# CH32F203RCT6-R1.net
KiCad netlist of a schematic drawn in Altium Designer
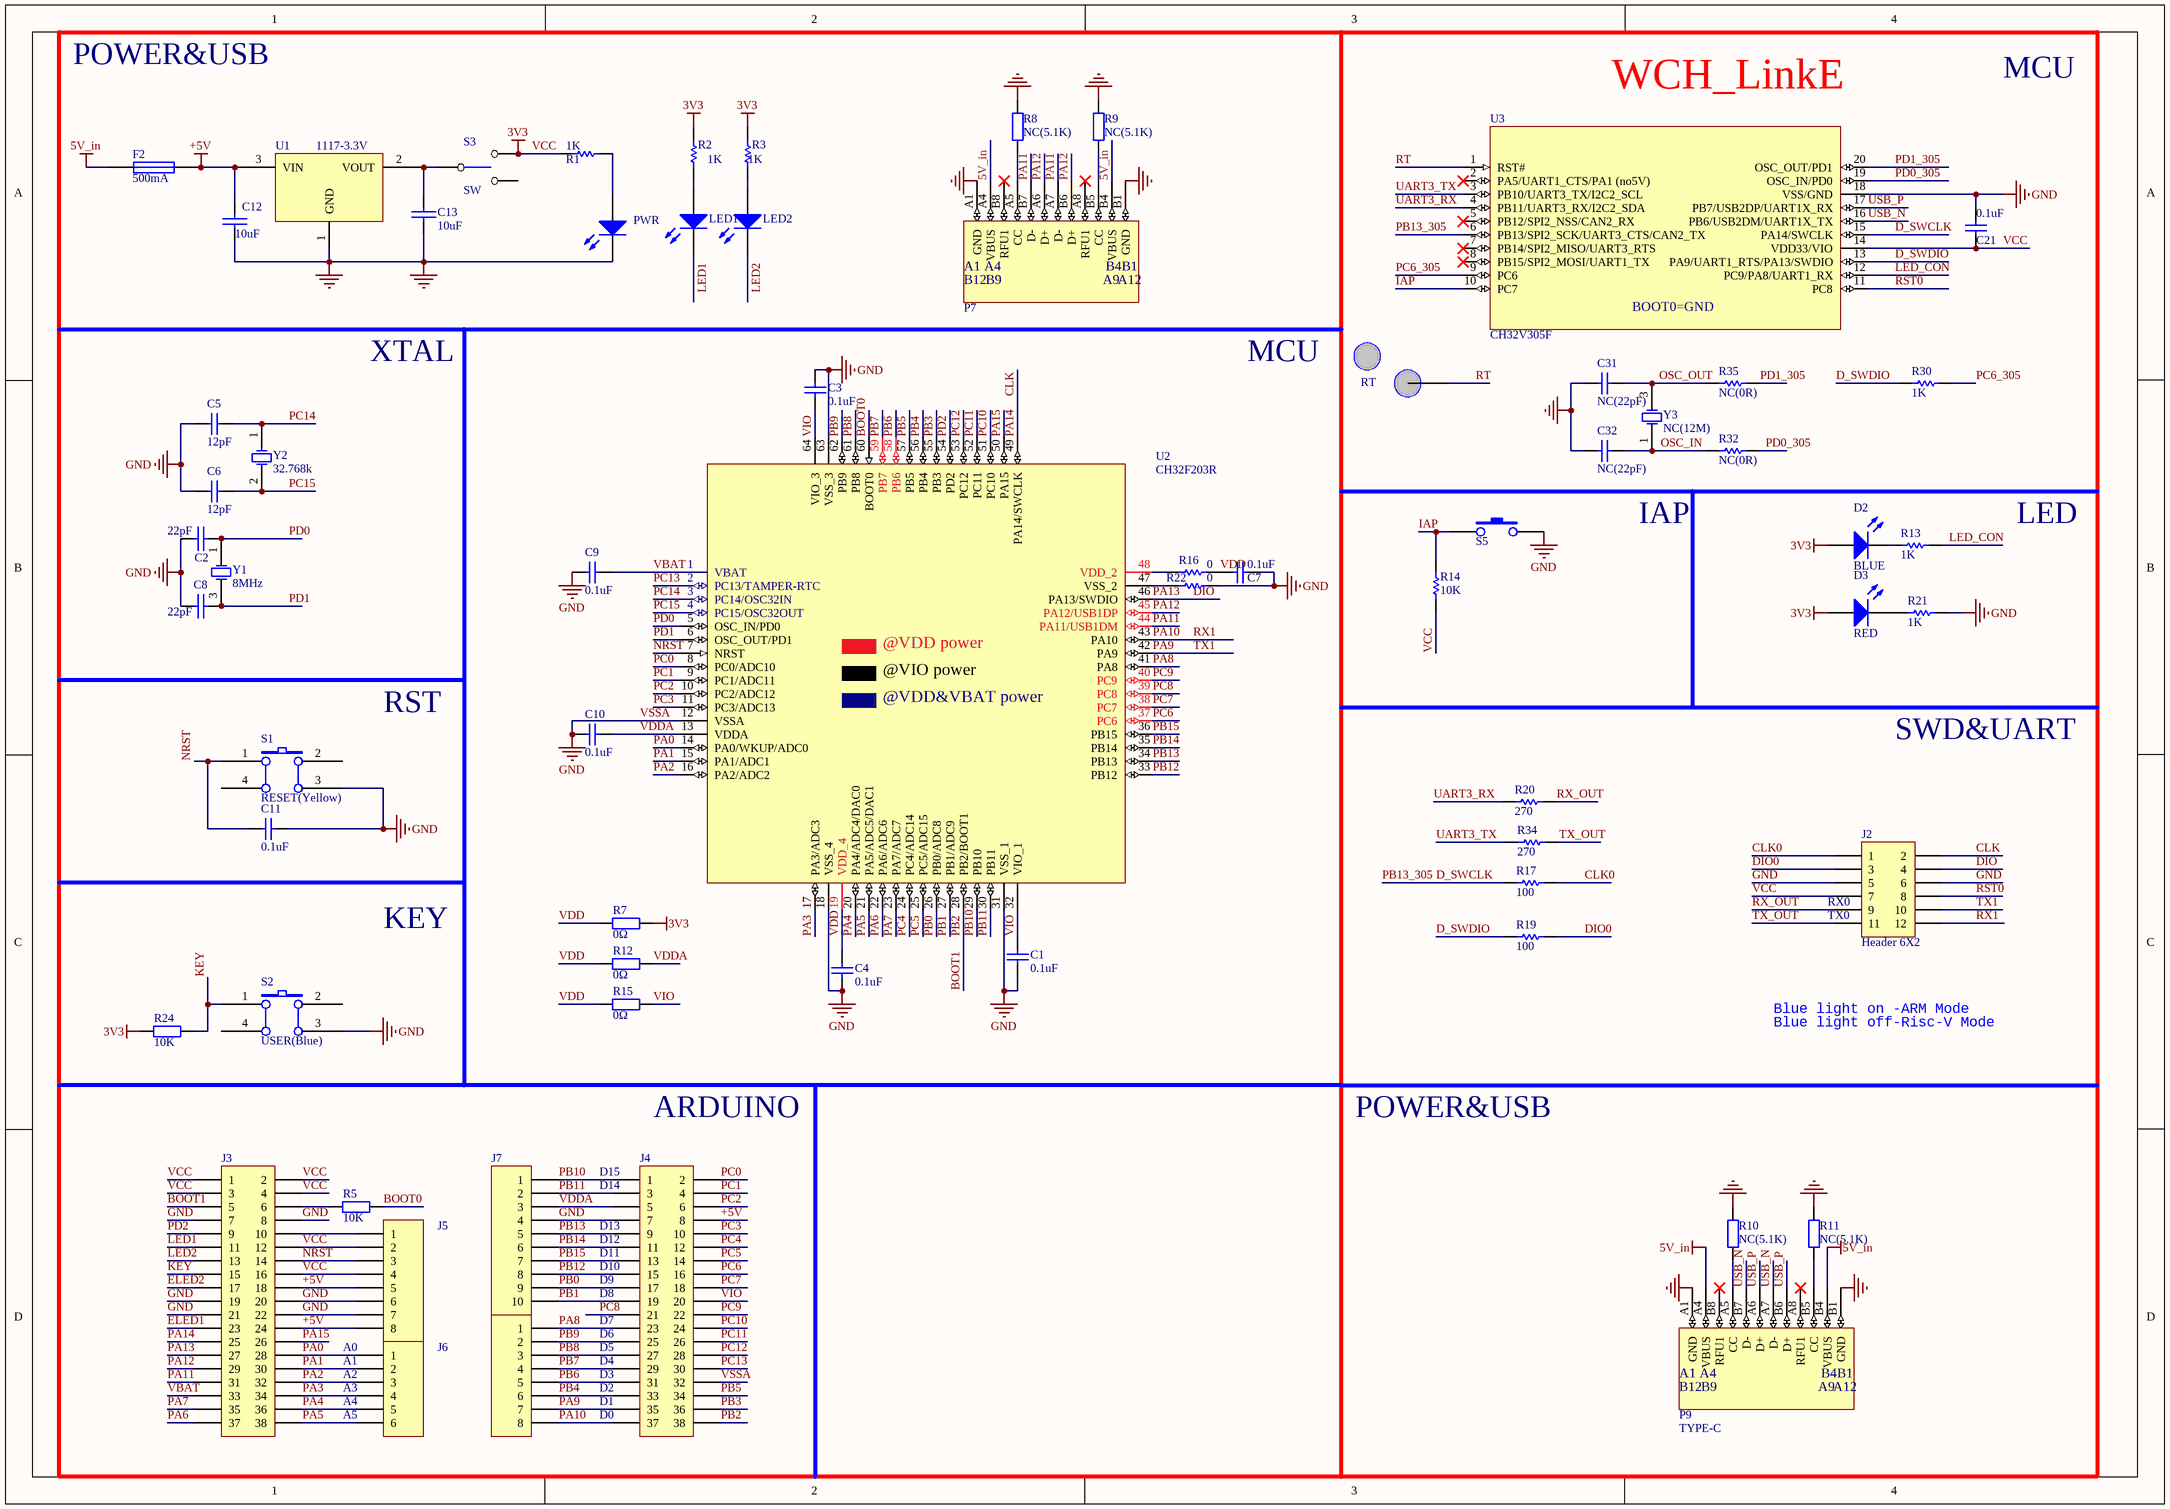
[diagram p0: CH32F203RCT6-R1.SchDoc]

(export (version "E")
  (design (tool "Eeschema 10.0.6"))
  (components
    (comp (ref "C1")
      (value "0.1uF")
      (footprint "0603_C")
      (description "Capacitor")
      (libsource (lib "Miscellaneous Devices") (part "Cap"))
    )
    (comp (ref "C2")
      (value "22pF")
      (footprint "0603_C")
      (description "Capacitor")
      (libsource (lib "*") (part "CAP"))
    )
    (comp (ref "C3")
      (value "0.1uF")
      (footprint "0603_C")
      (description "Capacitor")
      (libsource (lib "Miscellaneous Devices") (part "Cap"))
    )
    (comp (ref "C4")
      (value "0.1uF")
      (footprint "0603_C")
      (description "Capacitor")
      (libsource (lib "Miscellaneous Devices") (part "Cap"))
    )
    (comp (ref "C5")
      (value "12pF")
      (footprint "0603_C")
      (description "Capacitor")
      (libsource (lib "Miscellaneous Devices") (part "Cap"))
    )
    (comp (ref "C6")
      (value "12pF")
      (footprint "0603_C")
      (description "Capacitor")
      (libsource (lib "Miscellaneous Devices") (part "Cap"))
    )
    (comp (ref "C7")
      (value "0.1uF")
      (footprint "0603_C")
      (description "Capacitor")
      (libsource (lib "Miscellaneous Devices") (part "Cap"))
    )
    (comp (ref "C8")
      (value "22pF")
      (footprint "0603_C")
      (description "Capacitor")
      (libsource (lib "*") (part "CAP"))
    )
    (comp (ref "C9")
      (value "0.1uF")
      (footprint "0603_C")
      (description "Capacitor")
      (libsource (lib "Miscellaneous Devices") (part "Cap"))
    )
    (comp (ref "C10")
      (value "0.1uF")
      (footprint "0603_C")
      (description "Capacitor")
      (libsource (lib "Miscellaneous Devices") (part "Cap"))
    )
    (comp (ref "C11")
      (value "0.1uF")
      (footprint "0603_C")
      (description "Capacitor")
      (libsource (lib "Miscellaneous Devices") (part "Cap"))
    )
    (comp (ref "C12")
      (value "10uF")
      (footprint "3216_C")
      (description "Capacitor")
      (libsource (lib "*") (part "CAP"))
    )
    (comp (ref "C13")
      (value "10uF")
      (footprint "3216_C")
      (description "Capacitor")
      (libsource (lib "*") (part "CAP"))
    )
    (comp (ref "C21")
      (value "0.1uF")
      (footprint "0603_C")
      (description "Capacitor")
      (libsource (lib "Miscellaneous Devices") (part "Cap"))
    )
    (comp (ref "C31")
      (value "NC(22pF)")
      (footprint "0603_C")
      (description "Capacitor")
      (fields (field (name "PUBLISHER") "Altium Limited"))
      (libsource (lib "*") (part "Cap"))
    )
    (comp (ref "C32")
      (value "NC(22pF)")
      (footprint "0603_C")
      (description "Capacitor")
      (fields (field (name "PUBLISHER") "Altium Limited"))
      (libsource (lib "*") (part "Cap"))
    )
    (comp (ref "D2")
      (value "BLUE")
      (footprint "0603+")
      (description "Typical RED, GREEN, YELLOW, AMBER GaAs LED")
      (fields (field (name "PUBLISHER") "Altium Limited"))
      (libsource (lib "MYLIB") (part "D0603"))
    )
    (comp (ref "D3")
      (value "RED")
      (footprint "0603+")
      (description "Typical RED, GREEN, YELLOW, AMBER GaAs LED")
      (fields (field (name "PUBLISHER") "Altium Limited"))
      (libsource (lib "MYLIB") (part "D0603"))
    )
    (comp (ref "F2")
      (value "500mA")
      (footprint "0805")
      (description "Fuse")
      (libsource (lib "*") (part "FUSE1"))
    )
    (comp (ref "J2")
      (value "Header 6X2")
      (footprint "IDC12-2.54mm")
      (description "Header, 6-Pin, Dual row")
      (fields (field (name "PUBLISHER") "Altium Limited"))
      (libsource (lib "Miscellaneous Connectors") (part "Header 6X2"))
    )
    (comp (ref "J3")
      (value "Header 19X2")
      (footprint "IDC38-2.54mm")
      (description "Header, 19-Pin, Dual row")
      (fields (field (name "PUBLISHER") "Altium Limited"))
      (libsource (lib "Miscellaneous Connectors") (part "Header 19X2"))
    )
    (comp (ref "J4")
      (value "Header 19X2")
      (footprint "IDC38-2.54mm")
      (description "Header, 19-Pin, Dual row")
      (fields (field (name "PUBLISHER") "Altium Limited"))
      (libsource (lib "Miscellaneous Connectors") (part "Header 19X2"))
    )
    (comp (ref "J5")
      (value "Header 8")
      (footprint "SIP8-2.54mm")
      (description "Header, 8-Pin")
      (fields (field (name "PUBLISHER") "Altium Limited"))
      (libsource (lib "") (part "Header 8_1"))
    )
    (comp (ref "J6")
      (value "Header 6")
      (footprint "SIP6-2.54MM")
      (description "Header, 6-Pin")
      (fields (field (name "PUBLISHER") "Altium Limited"))
      (libsource (lib "Miscellaneous Connectors") (part "Header 6"))
    )
    (comp (ref "J7")
      (value "Header 10")
      (footprint "SIP10-2.54mm")
      (description "Header, 10-Pin")
      (fields (field (name "PUBLISHER") "Altium Limited"))
      (libsource (lib "Miscellaneous Connectors") (part "Header 10"))
    )
    (comp (ref "J8")
      (value "Header 8")
      (footprint "SIP8-2.54mm")
      (description "Header, 8-Pin")
      (fields (field (name "PUBLISHER") "Altium Limited"))
      (libsource (lib "Miscellaneous Connectors") (part "Header 8"))
    )
    (comp (ref "LED1")
      (value "LED1   blue")
      (footprint "0603+")
      (description "Typical INFRARED GaAs LED")
      (fields (field (name "PUBLISHER") "Altium Limited"))
      (libsource (lib "Miscellaneous Devices") (part "LED0"))
    )
    (comp (ref "LED2")
      (value "LED2  blue")
      (footprint "0603+")
      (description "Typical INFRARED GaAs LED")
      (fields (field (name "PUBLISHER") "Altium Limited"))
      (libsource (lib "Miscellaneous Devices") (part "LED0"))
    )
    (comp (ref "P7")
      (value "TYPE-C")
      (footprint "TYPE-C-Receptacle-2.0")
      (libsource (lib "*") (part "TYPE-C1"))
    )
    (comp (ref "P9")
      (value "TYPE-C")
      (footprint "TYPE-C-Receptacle-2.0")
      (libsource (lib "*") (part "TYPE-C1"))
    )
    (comp (ref "PWR")
      (value "POWER  red")
      (footprint "0603+")
      (description "Typical INFRARED GaAs LED")
      (fields (field (name "PUBLISHER") "Altium Limited"))
      (libsource (lib "Miscellaneous Devices") (part "LED0"))
    )
    (comp (ref "R1")
      (value "1K")
      (footprint "0603")
      (description "Semiconductor Resistor")
      (libsource (lib "Miscellaneous Devices") (part "Res Semi"))
    )
    (comp (ref "R2")
      (value "1K")
      (footprint "0603")
      (description "Semiconductor Resistor")
      (libsource (lib "Miscellaneous Devices") (part "Res Semi"))
    )
    (comp (ref "R3")
      (value "1K")
      (footprint "0603")
      (description "Semiconductor Resistor")
      (libsource (lib "Miscellaneous Devices") (part "Res Semi"))
    )
    (comp (ref "R5")
      (value "10K")
      (footprint "0603")
      (description "Resistor")
      (libsource (lib "") (part "Res2_3"))
    )
    (comp (ref "R7")
      (value "0Ω")
      (footprint "0603")
      (description "Resistor")
      (libsource (lib "") (part "Res2_1"))
    )
    (comp (ref "R8")
      (value "NC(5.1K)")
      (footprint "0603")
      (description "Resistor")
      (libsource (lib "Miscellaneous Devices") (part "Res2"))
    )
    (comp (ref "R9")
      (value "NC(5.1K)")
      (footprint "0603")
      (description "Resistor")
      (libsource (lib "Miscellaneous Devices") (part "Res2"))
    )
    (comp (ref "R10")
      (value "NC(5.1K)")
      (footprint "0603")
      (description "Resistor")
      (libsource (lib "") (part "Res2_2"))
    )
    (comp (ref "R11")
      (value "NC(5.1K)")
      (footprint "0603")
      (description "Resistor")
      (libsource (lib "") (part "Res2_2"))
    )
    (comp (ref "R12")
      (value "0Ω")
      (footprint "0603")
      (description "Resistor")
      (libsource (lib "") (part "Res2_1"))
    )
    (comp (ref "R13")
      (value "1K")
      (footprint "0603")
      (description "Resistor")
      (fields (field (name "PUBLISHER") "Altium Limited"))
      (libsource (lib "MYLIB") (part "0603-1"))
    )
    (comp (ref "R14")
      (value "10K")
      (footprint "0603")
      (description "Resistor")
      (fields (field (name "PUBLISHER") "Altium Limited"))
      (libsource (lib "MYLIB") (part "0603-1"))
    )
    (comp (ref "R15")
      (value "0Ω")
      (footprint "0603")
      (description "Resistor")
      (libsource (lib "") (part "Res2_1"))
    )
    (comp (ref "R16")
      (value "0")
      (footprint "0603")
      (description "Resistor")
      (fields (field (name "PUBLISHER") "Altium Limited"))
      (libsource (lib "MYLIB") (part "0603-1"))
    )
    (comp (ref "R17")
      (value "100")
      (footprint "0603")
      (description "Resistor")
      (fields (field (name "PUBLISHER") "Altium Limited"))
      (libsource (lib "MYLIB") (part "0603-1"))
    )
    (comp (ref "R19")
      (value "100")
      (footprint "0603")
      (description "Resistor")
      (fields (field (name "PUBLISHER") "Altium Limited"))
      (libsource (lib "MYLIB") (part "0603-1"))
    )
    (comp (ref "R20")
      (value "270")
      (footprint "0603")
      (description "Resistor")
      (fields (field (name "PUBLISHER") "Altium Limited"))
      (libsource (lib "MYLIB") (part "0603-1"))
    )
    (comp (ref "R21")
      (value "1K")
      (footprint "0603")
      (description "Resistor")
      (fields (field (name "PUBLISHER") "Altium Limited"))
      (libsource (lib "MYLIB") (part "0603-1"))
    )
    (comp (ref "R22")
      (value "0")
      (footprint "0603")
      (description "Resistor")
      (fields (field (name "PUBLISHER") "Altium Limited"))
      (libsource (lib "MYLIB") (part "0603-1"))
    )
    (comp (ref "R24")
      (value "10K")
      (footprint "0603")
      (description "Resistor")
      (libsource (lib "") (part "Res2_1"))
    )
    (comp (ref "R30")
      (value "1K")
      (footprint "0603")
      (description "Resistor")
      (fields (field (name "PUBLISHER") "Altium Limited"))
      (libsource (lib "MYLIB") (part "0603-1"))
    )
    (comp (ref "R32")
      (value "NC(0R)")
      (footprint "0603")
      (description "Resistor")
      (fields (field (name "PUBLISHER") "Altium Limited"))
      (libsource (lib "MYLIB") (part "0603-1"))
    )
    (comp (ref "R34")
      (value "270")
      (footprint "0603")
      (description "Resistor")
      (fields (field (name "PUBLISHER") "Altium Limited"))
      (libsource (lib "MYLIB") (part "0603-1"))
    )
    (comp (ref "R35")
      (value "NC(0R)")
      (footprint "0603")
      (description "Resistor")
      (fields (field (name "PUBLISHER") "Altium Limited"))
      (libsource (lib "MYLIB") (part "0603-1"))
    )
    (comp (ref "RT")
      (value "Testpoint")
      (footprint "TESTPOINT1")
      (description "测试点")
      (libsource (lib "wch_sch_others") (part "Testpoint"))
    )
    (comp (ref "S1")
      (value "RESET(Yellow)")
      (footprint "KEYX")
      (description "SE PUSHBUTTON")
      (libsource (lib "Documents") (part "SW PUSHBUTTON"))
    )
    (comp (ref "S2")
      (value "USER(Blue)")
      (footprint "KEYX")
      (description "SE PUSHBUTTON")
      (libsource (lib "Documents") (part "SW PUSHBUTTON"))
    )
    (comp (ref "S3") (value "SW") (footprint "SW1") (libsource (lib "MYSCH") (part "SW")))
    (comp (ref "S5") (value "KEY") (footprint "贴片按键") (libsource (lib "*") (part "KEY")))
    (comp (ref "U1")
      (value "1117-3.3V")
      (footprint "SOT-223")
      (libsource (lib "wch_sch_others") (part "1117-3.3V"))
    )
    (comp (ref "U2")
      (value "CH32F203R")
      (footprint "LQFP64M_10x10")
      (description "ARM M3 HD-MCU, 144MHz, 8*UART, 10*Timer, 4*OPA")
      (libsource (lib "CHXXX") (part "CH32F203R"))
    )
    (comp (ref "U3")
      (value "CH32V305F")
      (footprint "TSSOP20")
      (description "RISC-V FPU HD-MCU, 144MHz, USB_480M, CAN, UART*2, SPI")
      (libsource (lib "CHXXX") (part "CH32V305F"))
    )
    (comp (ref "Y1")
      (value "8MHz")
      (footprint "XT3225")
      (description "Crystal Oscillator")
      (fields (field (name "PUBLISHER") "Altium Limited"))
      (libsource (lib "*") (part "XTAL"))
    )
    (comp (ref "Y2")
      (value "32.768k")
      (footprint "FC-135")
      (description "Crystal Oscillator")
      (fields (field (name "PUBLISHER") "Altium Limited"))
      (libsource (lib "Miscellaneous Devices") (part "XTAL"))
    )
    (comp (ref "Y3")
      (value "NC(12M)")
      (footprint "XT3225")
      (description "Crystal Oscillator")
      (libsource (lib "*") (part "XTAL"))
    )
  )
  (nets
    (net (code "1") (name "+5V") (class "Default")
      (node (ref "C12") (pin "1") (pinfunction "1_1") (pintype "passive"))
      (node (ref "F2") (pin "2") (pinfunction "2_2") (pintype "passive"))
      (node (ref "J3") (pin "18") (pinfunction "18_18") (pintype "passive"))
      (node (ref "J3") (pin "24") (pinfunction "24_24") (pintype "passive"))
      (node (ref "J4") (pin "8") (pinfunction "8_8") (pintype "passive"))
      (node (ref "J5") (pin "5") (pinfunction "5_5") (pintype "passive"))
      (node (ref "J5") (pin "8") (pinfunction "8_8") (pintype "passive"))
      (node (ref "U1") (pin "3") (pinfunction "VIN_3") (pintype "passive"))
    )
    (net (code "2") (name "/BOOT0") (class "Default")
      (node (ref "R5") (pin "2") (pinfunction "2_2") (pintype "passive"))
      (node (ref "U2") (pin "60") (pinfunction "BOOT0_60") (pintype "input"))
    )
    (net (code "3") (name "/BOOT1") (class "Default")
      (node (ref "J3") (pin "5") (pinfunction "5_5") (pintype "passive"))
      (node (ref "J4") (pin "38") (pinfunction "38_38") (pintype "passive"))
      (node (ref "U2") (pin "28") (pinfunction "PB2/BOOT1_28") (pintype "bidirectional"))
    )
    (net (code "4") (name "/CLK") (class "Default")
      (node (ref "J2") (pin "2") (pinfunction "2_2") (pintype "passive"))
      (node (ref "J3") (pin "25") (pinfunction "25_25") (pintype "passive"))
      (node (ref "U2") (pin "49") (pinfunction "PA14/SWCLK_49") (pintype "bidirectional"))
    )
    (net (code "5") (name "/CLK0") (class "Default")
      (node (ref "J2") (pin "1") (pinfunction "1_1") (pintype "passive"))
      (node (ref "R17") (pin "1") (pinfunction "1_1") (pintype "passive"))
    )
    (net (code "6") (name "/DIO") (class "Default")
      (node (ref "J2") (pin "4") (pinfunction "4_4") (pintype "passive"))
      (node (ref "J3") (pin "27") (pinfunction "27_27") (pintype "passive"))
      (node (ref "U2") (pin "46") (pinfunction "PA13/SWDIO_46") (pintype "bidirectional"))
    )
    (net (code "7") (name "/DIO0") (class "Default")
      (node (ref "J2") (pin "3") (pinfunction "3_3") (pintype "passive"))
      (node (ref "R19") (pin "1") (pinfunction "1_1") (pintype "passive"))
    )
    (net (code "8") (name "/D_SWCLK") (class "Default")
      (node (ref "R17") (pin "2") (pinfunction "2_2") (pintype "passive"))
      (node (ref "U3") (pin "15") (pinfunction "PA14/SWCLK_15") (pintype "bidirectional"))
      (node (ref "U3") (pin "6") (pinfunction "PB13/SPI2_SCK/UART3_CTS/CAN2_TX_6") (pintype "bidirectional"))
    )
    (net (code "9") (name "/D_SWDIO") (class "Default")
      (node (ref "R19") (pin "2") (pinfunction "2_2") (pintype "passive"))
      (node (ref "R30") (pin "1") (pinfunction "1_1") (pintype "passive"))
      (node (ref "U3") (pin "13") (pinfunction "PA9/UART1_RTS/PA13/SWDIO_13") (pintype "bidirectional"))
    )
    (net (code "10") (name "/ELED1") (class "Default")
      (node (ref "J3") (pin "23") (pinfunction "23_23") (pintype "passive"))
    )
    (net (code "11") (name "/ELED2") (class "Default")
      (node (ref "J3") (pin "17") (pinfunction "17_17") (pintype "passive"))
    )
    (net (code "12") (name "/IAP") (class "Default")
      (node (ref "R14") (pin "1") (pinfunction "1_1") (pintype "passive"))
      (node (ref "S5") (pin "1") (pinfunction "1_1") (pintype "passive"))
      (node (ref "U3") (pin "10") (pinfunction "PC7_10") (pintype "bidirectional"))
    )
    (net (code "13") (name "/KEY") (class "Default")
      (node (ref "J3") (pin "15") (pinfunction "15_15") (pintype "passive"))
      (node (ref "R24") (pin "1") (pinfunction "1_1") (pintype "passive"))
      (node (ref "S2") (pin "1") (pinfunction "A0_1") (pintype "passive"))
    )
    (net (code "14") (name "/LED1") (class "Default")
      (node (ref "J3") (pin "11") (pinfunction "11_11") (pintype "passive"))
      (node (ref "LED1") (pin "2") (pinfunction "K_2") (pintype "passive"))
    )
    (net (code "15") (name "/LED2") (class "Default")
      (node (ref "J3") (pin "13") (pinfunction "13_13") (pintype "passive"))
      (node (ref "LED2") (pin "2") (pinfunction "K_2") (pintype "passive"))
    )
    (net (code "16") (name "/LED_CON") (class "Default")
      (node (ref "R13") (pin "1") (pinfunction "1_1") (pintype "passive"))
      (node (ref "U3") (pin "12") (pinfunction "PC9/PA8/UART1_RX_12") (pintype "bidirectional"))
    )
    (net (code "17") (name "/NRST") (class "Default")
      (node (ref "C11") (pin "2") (pinfunction "2_2") (pintype "passive"))
      (node (ref "J3") (pin "14") (pinfunction "14_14") (pintype "passive"))
      (node (ref "J5") (pin "3") (pinfunction "3_3") (pintype "passive"))
      (node (ref "S1") (pin "1") (pinfunction "A0_1") (pintype "passive"))
      (node (ref "U2") (pin "7") (pinfunction "NRST_7") (pintype "input"))
    )
    (net (code "18") (name "/OSC_IN") (class "Default")
      (node (ref "C32") (pin "2") (pinfunction "2_2") (pintype "passive"))
      (node (ref "R32") (pin "2") (pinfunction "2_2") (pintype "passive"))
      (node (ref "Y3") (pin "1") (pinfunction "OSC1_1") (pintype "passive"))
    )
    (net (code "19") (name "/OSC_OUT") (class "Default")
      (node (ref "C31") (pin "2") (pinfunction "2_2") (pintype "passive"))
      (node (ref "R35") (pin "2") (pinfunction "2_2") (pintype "passive"))
      (node (ref "Y3") (pin "3") (pinfunction "OSC2_3") (pintype "passive"))
    )
    (net (code "20") (name "/PA0") (class "Default")
      (node (ref "J3") (pin "28") (pinfunction "28_28") (pintype "passive"))
      (node (ref "J6") (pin "1") (pinfunction "1_1") (pintype "passive"))
      (node (ref "U2") (pin "14") (pinfunction "PA0/WKUP/ADC0_14") (pintype "bidirectional"))
    )
    (net (code "21") (name "/PA1") (class "Default")
      (node (ref "J3") (pin "30") (pinfunction "30_30") (pintype "passive"))
      (node (ref "J6") (pin "2") (pinfunction "2_2") (pintype "passive"))
      (node (ref "U2") (pin "15") (pinfunction "PA1/ADC1_15") (pintype "bidirectional"))
    )
    (net (code "22") (name "/PA2") (class "Default")
      (node (ref "J3") (pin "32") (pinfunction "32_32") (pintype "passive"))
      (node (ref "J6") (pin "3") (pinfunction "3_3") (pintype "passive"))
      (node (ref "U2") (pin "16") (pinfunction "PA2/ADC2_16") (pintype "bidirectional"))
    )
    (net (code "23") (name "/PA3") (class "Default")
      (node (ref "J3") (pin "34") (pinfunction "34_34") (pintype "passive"))
      (node (ref "J6") (pin "4") (pinfunction "4_4") (pintype "passive"))
      (node (ref "U2") (pin "17") (pinfunction "PA3/ADC3_17") (pintype "bidirectional"))
    )
    (net (code "24") (name "/PA4") (class "Default")
      (node (ref "J3") (pin "36") (pinfunction "36_36") (pintype "passive"))
      (node (ref "J6") (pin "5") (pinfunction "5_5") (pintype "passive"))
      (node (ref "U2") (pin "20") (pinfunction "PA4/ADC4/DAC0_20") (pintype "bidirectional"))
    )
    (net (code "25") (name "/PA5") (class "Default")
      (node (ref "J3") (pin "38") (pinfunction "38_38") (pintype "passive"))
      (node (ref "J6") (pin "6") (pinfunction "6_6") (pintype "passive"))
      (node (ref "U2") (pin "21") (pinfunction "PA5/ADC5/DAC1_21") (pintype "bidirectional"))
    )
    (net (code "26") (name "/PA6") (class "Default")
      (node (ref "J3") (pin "37") (pinfunction "37_37") (pintype "passive"))
      (node (ref "U2") (pin "22") (pinfunction "PA6/ADC6_22") (pintype "bidirectional"))
    )
    (net (code "27") (name "/PA7") (class "Default")
      (node (ref "J3") (pin "35") (pinfunction "35_35") (pintype "passive"))
      (node (ref "U2") (pin "23") (pinfunction "PA7/ADC7_23") (pintype "bidirectional"))
    )
    (net (code "28") (name "/PA8") (class "Default")
      (node (ref "J4") (pin "23") (pinfunction "23_23") (pintype "passive"))
      (node (ref "J8") (pin "1") (pinfunction "1_1") (pintype "passive"))
      (node (ref "U2") (pin "41") (pinfunction "PA8_41") (pintype "bidirectional"))
    )
    (net (code "29") (name "/PA9") (class "Default")
      (node (ref "J2") (pin "10") (pinfunction "10_10") (pintype "passive"))
      (node (ref "J4") (pin "35") (pinfunction "35_35") (pintype "passive"))
      (node (ref "J8") (pin "7") (pinfunction "7_7") (pintype "passive"))
      (node (ref "U2") (pin "42") (pinfunction "PA9_42") (pintype "bidirectional"))
    )
    (net (code "30") (name "/PA10") (class "Default")
      (node (ref "J2") (pin "12") (pinfunction "12_12") (pintype "passive"))
      (node (ref "J4") (pin "37") (pinfunction "37_37") (pintype "passive"))
      (node (ref "J8") (pin "8") (pinfunction "8_8") (pintype "passive"))
      (node (ref "U2") (pin "43") (pinfunction "PA10_43") (pintype "bidirectional"))
    )
    (net (code "31") (name "/PA11") (class "Default")
      (node (ref "J3") (pin "31") (pinfunction "31_31") (pintype "passive"))
      (node (ref "P7") (pin "A7") (pinfunction "D-_A7") (pintype "bidirectional"))
      (node (ref "P7") (pin "B7") (pinfunction "D-_B7") (pintype "bidirectional"))
      (node (ref "U2") (pin "44") (pinfunction "PA11/USB1DM_44") (pintype "bidirectional"))
    )
    (net (code "32") (name "/PA12") (class "Default")
      (node (ref "J3") (pin "29") (pinfunction "29_29") (pintype "passive"))
      (node (ref "P7") (pin "A6") (pinfunction "D+_A6") (pintype "bidirectional"))
      (node (ref "P7") (pin "B6") (pinfunction "D+_B6") (pintype "bidirectional"))
      (node (ref "U2") (pin "45") (pinfunction "PA12/USB1DP_45") (pintype "bidirectional"))
    )
    (net (code "33") (name "/PA15") (class "Default")
      (node (ref "J3") (pin "26") (pinfunction "26_26") (pintype "passive"))
      (node (ref "U2") (pin "50") (pinfunction "PA15_50") (pintype "bidirectional"))
    )
    (net (code "34") (name "/PB0") (class "Default")
      (node (ref "J4") (pin "17") (pinfunction "17_17") (pintype "passive"))
      (node (ref "J7") (pin "9") (pinfunction "9_9") (pintype "passive"))
      (node (ref "U2") (pin "26") (pinfunction "PB0/ADC8_26") (pintype "bidirectional"))
    )
    (net (code "35") (name "/PB1") (class "Default")
      (node (ref "J4") (pin "19") (pinfunction "19_19") (pintype "passive"))
      (node (ref "J7") (pin "10") (pinfunction "10_10") (pintype "passive"))
      (node (ref "U2") (pin "27") (pinfunction "PB1/ADC9_27") (pintype "bidirectional"))
    )
    (net (code "36") (name "/PB3") (class "Default")
      (node (ref "J4") (pin "36") (pinfunction "36_36") (pintype "passive"))
      (node (ref "U2") (pin "55") (pinfunction "PB3_55") (pintype "bidirectional"))
    )
    (net (code "37") (name "/PB4") (class "Default")
      (node (ref "J4") (pin "33") (pinfunction "33_33") (pintype "passive"))
      (node (ref "J8") (pin "6") (pinfunction "6_6") (pintype "passive"))
      (node (ref "U2") (pin "56") (pinfunction "PB4_56") (pintype "bidirectional"))
    )
    (net (code "38") (name "/PB5") (class "Default")
      (node (ref "J4") (pin "34") (pinfunction "34_34") (pintype "passive"))
      (node (ref "U2") (pin "57") (pinfunction "PB5_57") (pintype "bidirectional"))
    )
    (net (code "39") (name "/PB6") (class "Default")
      (node (ref "J4") (pin "31") (pinfunction "31_31") (pintype "passive"))
      (node (ref "J8") (pin "5") (pinfunction "5_5") (pintype "passive"))
      (node (ref "U2") (pin "58") (pinfunction "PB6_58") (pintype "bidirectional"))
    )
    (net (code "40") (name "/PB7") (class "Default")
      (node (ref "J4") (pin "29") (pinfunction "29_29") (pintype "passive"))
      (node (ref "J8") (pin "4") (pinfunction "4_4") (pintype "passive"))
      (node (ref "U2") (pin "59") (pinfunction "PB7_59") (pintype "bidirectional"))
    )
    (net (code "41") (name "/PB8") (class "Default")
      (node (ref "J4") (pin "27") (pinfunction "27_27") (pintype "passive"))
      (node (ref "J8") (pin "3") (pinfunction "3_3") (pintype "passive"))
      (node (ref "U2") (pin "61") (pinfunction "PB8_61") (pintype "bidirectional"))
    )
    (net (code "42") (name "/PB9") (class "Default")
      (node (ref "J4") (pin "25") (pinfunction "25_25") (pintype "passive"))
      (node (ref "J8") (pin "2") (pinfunction "2_2") (pintype "passive"))
      (node (ref "U2") (pin "62") (pinfunction "PB9_62") (pintype "bidirectional"))
    )
    (net (code "43") (name "/PB10") (class "Default")
      (node (ref "J4") (pin "1") (pinfunction "1_1") (pintype "passive"))
      (node (ref "J7") (pin "1") (pinfunction "1_1") (pintype "passive"))
      (node (ref "U2") (pin "29") (pinfunction "PB10_29") (pintype "bidirectional"))
    )
    (net (code "44") (name "/PB11") (class "Default")
      (node (ref "J4") (pin "3") (pinfunction "3_3") (pintype "passive"))
      (node (ref "J7") (pin "2") (pinfunction "2_2") (pintype "passive"))
      (node (ref "U2") (pin "30") (pinfunction "PB11_30") (pintype "bidirectional"))
    )
    (net (code "45") (name "/PB12") (class "Default")
      (node (ref "J4") (pin "15") (pinfunction "15_15") (pintype "passive"))
      (node (ref "J7") (pin "8") (pinfunction "8_8") (pintype "passive"))
      (node (ref "U2") (pin "33") (pinfunction "PB12_33") (pintype "bidirectional"))
    )
    (net (code "46") (name "/PB13") (class "Default")
      (node (ref "J4") (pin "9") (pinfunction "9_9") (pintype "passive"))
      (node (ref "J7") (pin "5") (pinfunction "5_5") (pintype "passive"))
      (node (ref "U2") (pin "34") (pinfunction "PB13_34") (pintype "bidirectional"))
    )
    (net (code "47") (name "/PB14") (class "Default")
      (node (ref "J4") (pin "11") (pinfunction "11_11") (pintype "passive"))
      (node (ref "J7") (pin "6") (pinfunction "6_6") (pintype "passive"))
      (node (ref "U2") (pin "35") (pinfunction "PB14_35") (pintype "bidirectional"))
    )
    (net (code "48") (name "/PB15") (class "Default")
      (node (ref "J4") (pin "13") (pinfunction "13_13") (pintype "passive"))
      (node (ref "J7") (pin "7") (pinfunction "7_7") (pintype "passive"))
      (node (ref "U2") (pin "36") (pinfunction "PB15_36") (pintype "bidirectional"))
    )
    (net (code "49") (name "/PC0") (class "Default")
      (node (ref "J4") (pin "2") (pinfunction "2_2") (pintype "passive"))
      (node (ref "U2") (pin "8") (pinfunction "PC0/ADC10_8") (pintype "bidirectional"))
    )
    (net (code "50") (name "/PC1") (class "Default")
      (node (ref "J4") (pin "4") (pinfunction "4_4") (pintype "passive"))
      (node (ref "U2") (pin "9") (pinfunction "PC1/ADC11_9") (pintype "bidirectional"))
    )
    (net (code "51") (name "/PC2") (class "Default")
      (node (ref "J4") (pin "6") (pinfunction "6_6") (pintype "passive"))
      (node (ref "U2") (pin "10") (pinfunction "PC2/ADC12_10") (pintype "bidirectional"))
    )
    (net (code "52") (name "/PC3") (class "Default")
      (node (ref "J4") (pin "10") (pinfunction "10_10") (pintype "passive"))
      (node (ref "U2") (pin "11") (pinfunction "PC3/ADC13_11") (pintype "bidirectional"))
    )
    (net (code "53") (name "/PC4") (class "Default")
      (node (ref "J4") (pin "12") (pinfunction "12_12") (pintype "passive"))
      (node (ref "U2") (pin "24") (pinfunction "PC4/ADC14_24") (pintype "bidirectional"))
    )
    (net (code "54") (name "/PC5") (class "Default")
      (node (ref "J4") (pin "14") (pinfunction "14_14") (pintype "passive"))
      (node (ref "U2") (pin "25") (pinfunction "PC5/ADC15_25") (pintype "bidirectional"))
    )
    (net (code "55") (name "/PC6") (class "Default")
      (node (ref "J4") (pin "16") (pinfunction "16_16") (pintype "passive"))
      (node (ref "U2") (pin "37") (pinfunction "PC6_37") (pintype "bidirectional"))
    )
    (net (code "56") (name "/PC6_305") (class "Default")
      (node (ref "R30") (pin "2") (pinfunction "2_2") (pintype "passive"))
      (node (ref "U3") (pin "9") (pinfunction "PC6_9") (pintype "bidirectional"))
    )
    (net (code "57") (name "/PC7") (class "Default")
      (node (ref "J4") (pin "18") (pinfunction "18_18") (pintype "passive"))
      (node (ref "U2") (pin "38") (pinfunction "PC7_38") (pintype "bidirectional"))
    )
    (net (code "58") (name "/PC8") (class "Default")
      (node (ref "J4") (pin "21") (pinfunction "21_21") (pintype "passive"))
      (node (ref "U2") (pin "39") (pinfunction "PC8_39") (pintype "bidirectional"))
    )
    (net (code "59") (name "/PC9") (class "Default")
      (node (ref "J4") (pin "22") (pinfunction "22_22") (pintype "passive"))
      (node (ref "U2") (pin "40") (pinfunction "PC9_40") (pintype "bidirectional"))
    )
    (net (code "60") (name "/PC10") (class "Default")
      (node (ref "J4") (pin "24") (pinfunction "24_24") (pintype "passive"))
      (node (ref "U2") (pin "51") (pinfunction "PC10_51") (pintype "bidirectional"))
    )
    (net (code "61") (name "/PC11") (class "Default")
      (node (ref "J4") (pin "26") (pinfunction "26_26") (pintype "passive"))
      (node (ref "U2") (pin "52") (pinfunction "PC11_52") (pintype "bidirectional"))
    )
    (net (code "62") (name "/PC12") (class "Default")
      (node (ref "J4") (pin "28") (pinfunction "28_28") (pintype "passive"))
      (node (ref "U2") (pin "53") (pinfunction "PC12_53") (pintype "bidirectional"))
    )
    (net (code "63") (name "/PC13") (class "Default")
      (node (ref "J4") (pin "30") (pinfunction "30_30") (pintype "passive"))
      (node (ref "U2") (pin "2") (pinfunction "PC13/TAMPER-RTC_2") (pintype "bidirectional"))
    )
    (net (code "64") (name "/PC14") (class "Default")
      (node (ref "C5") (pin "1") (pinfunction "1_1") (pintype "passive"))
      (node (ref "U2") (pin "3") (pinfunction "PC14/OSC32IN_3") (pintype "bidirectional"))
      (node (ref "Y2") (pin "1") (pinfunction "OSC1_1") (pintype "passive"))
    )
    (net (code "65") (name "/PC15") (class "Default")
      (node (ref "C6") (pin "1") (pinfunction "1_1") (pintype "passive"))
      (node (ref "U2") (pin "4") (pinfunction "PC15/OSC32OUT_4") (pintype "bidirectional"))
      (node (ref "Y2") (pin "2") (pinfunction "OSC2_2") (pintype "passive"))
    )
    (net (code "66") (name "/PD0") (class "Default")
      (node (ref "C2") (pin "2") (pinfunction "2_2") (pintype "passive"))
      (node (ref "U2") (pin "5") (pinfunction "OSC_IN/PD0_5") (pintype "bidirectional"))
      (node (ref "Y1") (pin "1") (pinfunction "OSC1_1") (pintype "passive"))
    )
    (net (code "67") (name "/PD0_305") (class "Default")
      (node (ref "R32") (pin "1") (pinfunction "1_1") (pintype "passive"))
      (node (ref "U3") (pin "19") (pinfunction "OSC_IN/PD0_19") (pintype "bidirectional"))
    )
    (net (code "68") (name "/PD1") (class "Default")
      (node (ref "C8") (pin "2") (pinfunction "2_2") (pintype "passive"))
      (node (ref "U2") (pin "6") (pinfunction "OSC_OUT/PD1_6") (pintype "bidirectional"))
      (node (ref "Y1") (pin "3") (pinfunction "OSC2_3") (pintype "passive"))
    )
    (net (code "69") (name "/PD1_305") (class "Default")
      (node (ref "R35") (pin "1") (pinfunction "1_1") (pintype "passive"))
      (node (ref "U3") (pin "20") (pinfunction "OSC_OUT/PD1_20") (pintype "bidirectional"))
    )
    (net (code "70") (name "/PD2") (class "Default")
      (node (ref "J3") (pin "9") (pinfunction "9_9") (pintype "passive"))
      (node (ref "U2") (pin "54") (pinfunction "PD2_54") (pintype "bidirectional"))
    )
    (net (code "71") (name "/RST0") (class "Default")
      (node (ref "J2") (pin "8") (pinfunction "8_8") (pintype "passive"))
      (node (ref "U3") (pin "11") (pinfunction "PC8_11") (pintype "bidirectional"))
    )
    (net (code "72") (name "/RT") (class "Default")
      (node (ref "RT") (pin "1") (pinfunction "point_1") (pintype "passive"))
      (node (ref "U3") (pin "1") (pinfunction "RST#_1") (pintype "input"))
    )
    (net (code "73") (name "/RX_OUT") (class "Default")
      (node (ref "J2") (pin "9") (pinfunction "9_9") (pintype "passive"))
      (node (ref "R20") (pin "1") (pinfunction "1_1") (pintype "passive"))
    )
    (net (code "74") (name "/TX_OUT") (class "Default")
      (node (ref "J2") (pin "11") (pinfunction "11_11") (pintype "passive"))
      (node (ref "R34") (pin "1") (pinfunction "1_1") (pintype "passive"))
    )
    (net (code "75") (name "/UART3_RX") (class "Default")
      (node (ref "R20") (pin "2") (pinfunction "2_2") (pintype "passive"))
      (node (ref "U3") (pin "4") (pinfunction "PB11/UART3_RX/I2C2_SDA_4") (pintype "bidirectional"))
    )
    (net (code "76") (name "/UART3_TX") (class "Default")
      (node (ref "R34") (pin "2") (pinfunction "2_2") (pintype "passive"))
      (node (ref "U3") (pin "3") (pinfunction "PB10/UART3_TX/I2C2_SCL_3") (pintype "bidirectional"))
    )
    (net (code "77") (name "/USB_N") (class "Default")
      (node (ref "P9") (pin "A7") (pinfunction "D-_A7") (pintype "bidirectional"))
      (node (ref "P9") (pin "B7") (pinfunction "D-_B7") (pintype "bidirectional"))
      (node (ref "U3") (pin "16") (pinfunction "PB6/USB2DM/UART1X_TX_16") (pintype "bidirectional"))
    )
    (net (code "78") (name "/USB_P") (class "Default")
      (node (ref "P9") (pin "A6") (pinfunction "D+_A6") (pintype "bidirectional"))
      (node (ref "P9") (pin "B6") (pinfunction "D+_B6") (pintype "bidirectional"))
      (node (ref "U3") (pin "17") (pinfunction "PB7/USB2DP/UART1X_RX_17") (pintype "bidirectional"))
    )
    (net (code "79") (name "/VBAT") (class "Default")
      (node (ref "C9") (pin "1") (pinfunction "1_1") (pintype "passive"))
      (node (ref "J3") (pin "33") (pinfunction "33_33") (pintype "passive"))
      (node (ref "U2") (pin "1") (pinfunction "VBAT_1") (pintype "power_in"))
    )
    (net (code "80") (name "/VDD") (class "Default")
      (node (ref "C4") (pin "2") (pinfunction "2_2") (pintype "passive"))
      (node (ref "C7") (pin "2") (pinfunction "2_2") (pintype "passive"))
      (node (ref "R12") (pin "2") (pinfunction "2_2") (pintype "passive"))
      (node (ref "R15") (pin "2") (pinfunction "2_2") (pintype "passive"))
      (node (ref "R16") (pin "1") (pinfunction "1_1") (pintype "passive"))
      (node (ref "R7") (pin "2") (pinfunction "2_2") (pintype "passive"))
      (node (ref "U2") (pin "19") (pinfunction "VDD_4_19") (pintype "power_in"))
    )
    (net (code "81") (name "/VDDA") (class "Default")
      (node (ref "C10") (pin "1") (pinfunction "1_1") (pintype "passive"))
      (node (ref "J4") (pin "5") (pinfunction "5_5") (pintype "passive"))
      (node (ref "J7") (pin "3") (pinfunction "3_3") (pintype "passive"))
      (node (ref "R12") (pin "1") (pinfunction "1_1") (pintype "passive"))
      (node (ref "U2") (pin "13") (pinfunction "VDDA_13") (pintype "power_in"))
    )
    (net (code "82") (name "/VIO") (class "Default")
      (node (ref "C1") (pin "2") (pinfunction "2_2") (pintype "passive"))
      (node (ref "C3") (pin "2") (pinfunction "2_2") (pintype "passive"))
      (node (ref "J4") (pin "20") (pinfunction "20_20") (pintype "passive"))
      (node (ref "R15") (pin "1") (pinfunction "1_1") (pintype "passive"))
      (node (ref "U2") (pin "32") (pinfunction "VIO_1_32") (pintype "power_in"))
      (node (ref "U2") (pin "64") (pinfunction "VIO_3_64") (pintype "power_in"))
    )
    (net (code "83") (name "3V3") (class "Default")
      (node (ref "C21") (pin "1") (pinfunction "1_1") (pintype "passive"))
      (node (ref "D2") (pin "1") (pinfunction "A_1") (pintype "passive"))
      (node (ref "D3") (pin "1") (pinfunction "A_1") (pintype "passive"))
      (node (ref "J2") (pin "7") (pinfunction "7_7") (pintype "passive"))
      (node (ref "J3") (pin "1") (pinfunction "1_1") (pintype "passive"))
      (node (ref "J3") (pin "12") (pinfunction "12_12") (pintype "passive"))
      (node (ref "J3") (pin "16") (pinfunction "16_16") (pintype "passive"))
      (node (ref "J3") (pin "2") (pinfunction "2_2") (pintype "passive"))
      (node (ref "J3") (pin "3") (pinfunction "3_3") (pintype "passive"))
      (node (ref "J3") (pin "4") (pinfunction "4_4") (pintype "passive"))
      (node (ref "J5") (pin "2") (pinfunction "2_2") (pintype "passive"))
      (node (ref "J5") (pin "4") (pinfunction "4_4") (pintype "passive"))
      (node (ref "R1") (pin "2") (pinfunction "2_2") (pintype "passive"))
      (node (ref "R14") (pin "2") (pinfunction "2_2") (pintype "passive"))
      (node (ref "R2") (pin "1") (pinfunction "1_1") (pintype "passive"))
      (node (ref "R24") (pin "2") (pinfunction "2_2") (pintype "passive"))
      (node (ref "R3") (pin "1") (pinfunction "1_1") (pintype "passive"))
      (node (ref "R7") (pin "1") (pinfunction "1_1") (pintype "passive"))
      (node (ref "S3") (pin "3") (pinfunction "3_3") (pintype "passive"))
      (node (ref "U3") (pin "14") (pinfunction "VDD33/VIO_14") (pintype "power_in"))
    )
    (net (code "84") (name "5V_in") (class "Default")
      (node (ref "F2") (pin "1") (pinfunction "1_1") (pintype "passive"))
      (node (ref "P7") (pin "A4") (pinfunction "VBUS_A4") (pintype "bidirectional"))
      (node (ref "P7") (pin "B4") (pinfunction "VBUS_B4") (pintype "bidirectional"))
      (node (ref "P9") (pin "A4") (pinfunction "VBUS_A4") (pintype "bidirectional"))
      (node (ref "P9") (pin "B4") (pinfunction "VBUS_B4") (pintype "bidirectional"))
    )
    (net (code "85") (name "GND") (class "Default")
      (node (ref "C1") (pin "1") (pinfunction "1_1") (pintype "passive"))
      (node (ref "C10") (pin "2") (pinfunction "2_2") (pintype "passive"))
      (node (ref "C11") (pin "1") (pinfunction "1_1") (pintype "passive"))
      (node (ref "C12") (pin "2") (pinfunction "2_2") (pintype "passive"))
      (node (ref "C13") (pin "2") (pinfunction "2_2") (pintype "passive"))
      (node (ref "C2") (pin "1") (pinfunction "1_1") (pintype "passive"))
      (node (ref "C21") (pin "2") (pinfunction "2_2") (pintype "passive"))
      (node (ref "C3") (pin "1") (pinfunction "1_1") (pintype "passive"))
      (node (ref "C31") (pin "1") (pinfunction "1_1") (pintype "passive"))
      (node (ref "C32") (pin "1") (pinfunction "1_1") (pintype "passive"))
      (node (ref "C4") (pin "1") (pinfunction "1_1") (pintype "passive"))
      (node (ref "C5") (pin "2") (pinfunction "2_2") (pintype "passive"))
      (node (ref "C6") (pin "2") (pinfunction "2_2") (pintype "passive"))
      (node (ref "C7") (pin "1") (pinfunction "1_1") (pintype "passive"))
      (node (ref "C8") (pin "1") (pinfunction "1_1") (pintype "passive"))
      (node (ref "C9") (pin "2") (pinfunction "2_2") (pintype "passive"))
      (node (ref "J2") (pin "5") (pinfunction "5_5") (pintype "passive"))
      (node (ref "J2") (pin "6") (pinfunction "6_6") (pintype "passive"))
      (node (ref "J3") (pin "19") (pinfunction "19_19") (pintype "passive"))
      (node (ref "J3") (pin "20") (pinfunction "20_20") (pintype "passive"))
      (node (ref "J3") (pin "21") (pinfunction "21_21") (pintype "passive"))
      (node (ref "J3") (pin "22") (pinfunction "22_22") (pintype "passive"))
      (node (ref "J3") (pin "7") (pinfunction "7_7") (pintype "passive"))
      (node (ref "J3") (pin "8") (pinfunction "8_8") (pintype "passive"))
      (node (ref "J4") (pin "32") (pinfunction "32_32") (pintype "passive"))
      (node (ref "J4") (pin "7") (pinfunction "7_7") (pintype "passive"))
      (node (ref "J5") (pin "6") (pinfunction "6_6") (pintype "passive"))
      (node (ref "J5") (pin "7") (pinfunction "7_7") (pintype "passive"))
      (node (ref "J7") (pin "4") (pinfunction "4_4") (pintype "passive"))
      (node (ref "P7") (pin "A1") (pinfunction "GND_A1") (pintype "bidirectional"))
      (node (ref "P7") (pin "B1") (pinfunction "GND_B1") (pintype "bidirectional"))
      (node (ref "P9") (pin "A1") (pinfunction "GND_A1") (pintype "bidirectional"))
      (node (ref "P9") (pin "B1") (pinfunction "GND_B1") (pintype "bidirectional"))
      (node (ref "PWR") (pin "2") (pinfunction "K_2") (pintype "passive"))
      (node (ref "R10") (pin "2") (pinfunction "2_2") (pintype "passive"))
      (node (ref "R11") (pin "2") (pinfunction "2_2") (pintype "passive"))
      (node (ref "R21") (pin "1") (pinfunction "1_1") (pintype "passive"))
      (node (ref "R22") (pin "1") (pinfunction "1_1") (pintype "passive"))
      (node (ref "R8") (pin "1") (pinfunction "1_1") (pintype "passive"))
      (node (ref "R9") (pin "1") (pinfunction "1_1") (pintype "passive"))
      (node (ref "S1") (pin "3") (pinfunction "B1_3") (pintype "passive"))
      (node (ref "S2") (pin "3") (pinfunction "B1_3") (pintype "passive"))
      (node (ref "S5") (pin "2") (pinfunction "2_2") (pintype "passive"))
      (node (ref "U1") (pin "1") (pinfunction "GND_1") (pintype "passive"))
      (node (ref "U2") (pin "12") (pinfunction "VSSA_12") (pintype "power_in"))
      (node (ref "U2") (pin "18") (pinfunction "VSS_4_18") (pintype "power_in"))
      (node (ref "U2") (pin "31") (pinfunction "VSS_1_31") (pintype "power_in"))
      (node (ref "U2") (pin "63") (pinfunction "VSS_3_63") (pintype "power_in"))
      (node (ref "U3") (pin "18") (pinfunction "VSS/GND_18") (pintype "power_in"))
    )
    (net (code "86") (name "Net-(D2-K)") (class "Default")
      (node (ref "D2") (pin "2") (pinfunction "K_2") (pintype "passive"))
      (node (ref "R13") (pin "2") (pinfunction "2_2") (pintype "passive"))
    )
    (net (code "87") (name "Net-(D3-K)") (class "Default")
      (node (ref "D3") (pin "2") (pinfunction "K_2") (pintype "passive"))
      (node (ref "R21") (pin "2") (pinfunction "2_2") (pintype "passive"))
    )
    (net (code "88") (name "Net-(J3-Pad6)") (class "Default")
      (node (ref "J3") (pin "6") (pinfunction "6_6") (pintype "passive"))
      (node (ref "R5") (pin "1") (pinfunction "1_1") (pintype "passive"))
    )
    (net (code "89") (name "Net-(J3-Pad10)") (class "Default")
      (node (ref "J3") (pin "10") (pinfunction "10_10") (pintype "passive"))
      (node (ref "J5") (pin "1") (pinfunction "1_1") (pintype "passive"))
    )
    (net (code "90") (name "Net-(LED1-A)") (class "Default")
      (node (ref "LED1") (pin "1") (pinfunction "A_1") (pintype "passive"))
      (node (ref "R2") (pin "2") (pinfunction "2_2") (pintype "passive"))
    )
    (net (code "91") (name "Net-(LED2-A)") (class "Default")
      (node (ref "LED2") (pin "1") (pinfunction "A_1") (pintype "passive"))
      (node (ref "R3") (pin "2") (pinfunction "2_2") (pintype "passive"))
    )
    (net (code "92") (name "Net-(P7-CC-PadA5)") (class "Default")
      (node (ref "P7") (pin "A5") (pinfunction "CC_A5") (pintype "bidirectional"))
      (node (ref "R8") (pin "2") (pinfunction "2_2") (pintype "passive"))
    )
    (net (code "93") (name "Net-(P7-CC-PadB5)") (class "Default")
      (node (ref "P7") (pin "B5") (pinfunction "CC_B5") (pintype "bidirectional"))
      (node (ref "R9") (pin "2") (pinfunction "2_2") (pintype "passive"))
    )
    (net (code "94") (name "Net-(P9-CC-PadA5)") (class "Default")
      (node (ref "P9") (pin "A5") (pinfunction "CC_A5") (pintype "bidirectional"))
      (node (ref "R10") (pin "1") (pinfunction "1_1") (pintype "passive"))
    )
    (net (code "95") (name "Net-(P9-CC-PadB5)") (class "Default")
      (node (ref "P9") (pin "B5") (pinfunction "CC_B5") (pintype "bidirectional"))
      (node (ref "R11") (pin "1") (pinfunction "1_1") (pintype "passive"))
    )
    (net (code "96") (name "Net-(PWR-A)") (class "Default")
      (node (ref "PWR") (pin "1") (pinfunction "A_1") (pintype "passive"))
      (node (ref "R1") (pin "1") (pinfunction "1_1") (pintype "passive"))
    )
    (net (code "97") (name "Net-(U1-VOUT)") (class "Default")
      (node (ref "C13") (pin "1") (pinfunction "1_1") (pintype "passive"))
      (node (ref "S3") (pin "1") (pinfunction "1_1") (pintype "passive"))
      (node (ref "U1") (pin "2") (pinfunction "VOUT_2") (pintype "passive"))
    )
    (net (code "98") (name "Net-(U2-VDD_2)") (class "Default")
      (node (ref "R16") (pin "2") (pinfunction "2_2") (pintype "passive"))
      (node (ref "U2") (pin "48") (pinfunction "VDD_2_48") (pintype "power_in"))
    )
    (net (code "99") (name "Net-(U2-VSS_2)") (class "Default")
      (node (ref "R22") (pin "2") (pinfunction "2_2") (pintype "passive"))
      (node (ref "U2") (pin "47") (pinfunction "VSS_2_47") (pintype "power_in"))
    )
    (net (code "100") (name "unconnected-(P7-RFU1-PadA8)") (class "Default")
      (node (ref "P7") (pin "A8") (pinfunction "RFU1_A8") (pintype "bidirectional+no_connect"))
    )
    (net (code "101") (name "unconnected-(P7-RFU1-PadB8)") (class "Default")
      (node (ref "P7") (pin "B8") (pinfunction "RFU1_B8") (pintype "bidirectional+no_connect"))
    )
    (net (code "102") (name "unconnected-(P9-RFU1-PadA8)") (class "Default")
      (node (ref "P9") (pin "A8") (pinfunction "RFU1_A8") (pintype "bidirectional+no_connect"))
    )
    (net (code "103") (name "unconnected-(P9-RFU1-PadB8)") (class "Default")
      (node (ref "P9") (pin "B8") (pinfunction "RFU1_B8") (pintype "bidirectional+no_connect"))
    )
    (net (code "104") (name "unconnected-(S1-A1-Pad4)") (class "Default")
      (node (ref "S1") (pin "4") (pinfunction "A1_4") (pintype "passive"))
    )
    (net (code "105") (name "unconnected-(S1-B0-Pad2)") (class "Default")
      (node (ref "S1") (pin "2") (pinfunction "B0_2") (pintype "passive"))
    )
    (net (code "106") (name "unconnected-(S2-A1-Pad4)") (class "Default")
      (node (ref "S2") (pin "4") (pinfunction "A1_4") (pintype "passive"))
    )
    (net (code "107") (name "unconnected-(S2-B0-Pad2)") (class "Default")
      (node (ref "S2") (pin "2") (pinfunction "B0_2") (pintype "passive"))
    )
    (net (code "108") (name "unconnected-(S3-Pad2)") (class "Default")
      (node (ref "S3") (pin "2") (pinfunction "2_2") (pintype "passive"))
    )
    (net (code "109") (name "unconnected-(U3-PA5{slash}UART1_CTS{slash}PA1_(no5V)-Pad2)") (class "Default")
      (node (ref "U3") (pin "2") (pinfunction "PA5/UART1_CTS/PA1_(no5V)_2") (pintype "bidirectional+no_connect"))
    )
    (net (code "110") (name "unconnected-(U3-PB12{slash}SPI2_NSS{slash}CAN2_RX-Pad5)") (class "Default")
      (node (ref "U3") (pin "5") (pinfunction "PB12/SPI2_NSS/CAN2_RX_5") (pintype "bidirectional+no_connect"))
    )
    (net (code "111") (name "unconnected-(U3-PB14{slash}SPI2_MISO{slash}UART3_RTS-Pad7)") (class "Default")
      (node (ref "U3") (pin "7") (pinfunction "PB14/SPI2_MISO/UART3_RTS_7") (pintype "bidirectional+no_connect"))
    )
    (net (code "112") (name "unconnected-(U3-PB15{slash}SPI2_MOSI{slash}UART1_TX-Pad8)") (class "Default")
      (node (ref "U3") (pin "8") (pinfunction "PB15/SPI2_MOSI/UART1_TX_8") (pintype "bidirectional+no_connect"))
    )
  )
)
